# W050C.net
KiCad netlist of a schematic drawn in EAGLE
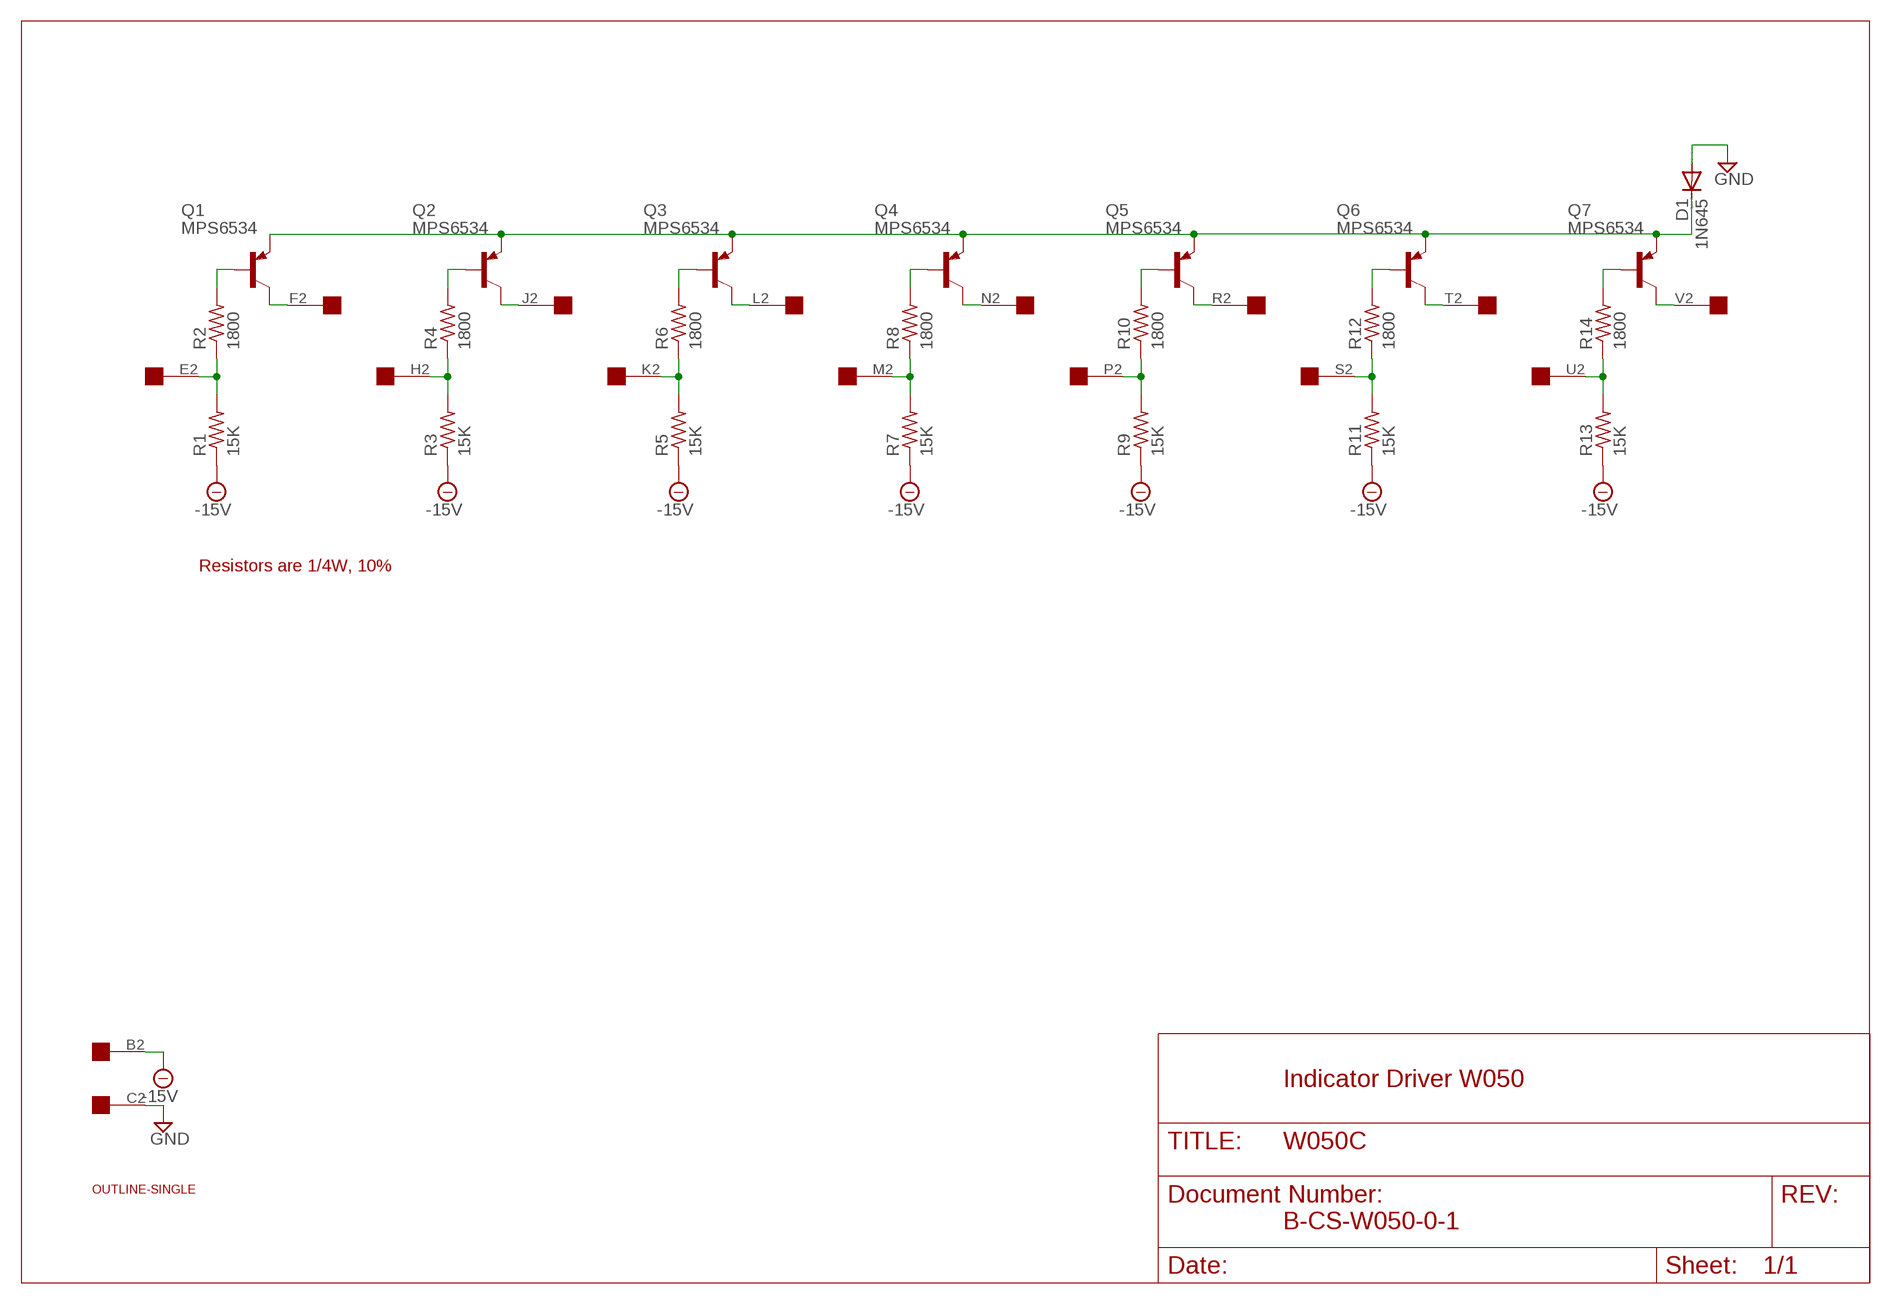
[diagram p0: schematic, sheet 1]

(export (version "E")
  (design (tool "Eeschema 10.0.6"))
  (components
    (comp (ref "D1")
      (value "1N645")
      (footprint "eagle-import:DO35-10")
      (libsource (lib "eagle-import") (part "1N4148DO35-10"))
    )
    (comp (ref "EDGE")
      (value "EDGE-1")
      (footprint "eagle-import:EDGE-CON1")
      (libsource (lib "eagle-import") (part "EDGE-1"))
    )
    (comp (ref "Q1")
      (value "MPS6534")
      (footprint "eagle-import:TO39")
      (libsource (lib "eagle-import") (part "2N2904"))
    )
    (comp (ref "Q2")
      (value "MPS6534")
      (footprint "eagle-import:TO39")
      (libsource (lib "eagle-import") (part "2N2904"))
    )
    (comp (ref "Q3")
      (value "MPS6534")
      (footprint "eagle-import:TO39")
      (libsource (lib "eagle-import") (part "2N2904"))
    )
    (comp (ref "Q4")
      (value "MPS6534")
      (footprint "eagle-import:TO39")
      (libsource (lib "eagle-import") (part "2N2904"))
    )
    (comp (ref "Q5")
      (value "MPS6534")
      (footprint "eagle-import:TO39")
      (libsource (lib "eagle-import") (part "2N2904"))
    )
    (comp (ref "Q6")
      (value "MPS6534")
      (footprint "eagle-import:TO39")
      (libsource (lib "eagle-import") (part "2N2904"))
    )
    (comp (ref "Q7")
      (value "MPS6534")
      (footprint "eagle-import:TO39")
      (libsource (lib "eagle-import") (part "2N2904"))
    )
    (comp (ref "R1")
      (value "15K")
      (footprint "eagle-import:0207_10")
      (libsource (lib "eagle-import") (part "R-US_0207/10"))
    )
    (comp (ref "R2")
      (value "1800")
      (footprint "eagle-import:0207_10")
      (libsource (lib "eagle-import") (part "R-US_0207/10"))
    )
    (comp (ref "R3")
      (value "15K")
      (footprint "eagle-import:0207_10")
      (libsource (lib "eagle-import") (part "R-US_0207/10"))
    )
    (comp (ref "R4")
      (value "1800")
      (footprint "eagle-import:0207_10")
      (libsource (lib "eagle-import") (part "R-US_0207/10"))
    )
    (comp (ref "R5")
      (value "15K")
      (footprint "eagle-import:0207_10")
      (libsource (lib "eagle-import") (part "R-US_0207/10"))
    )
    (comp (ref "R6")
      (value "1800")
      (footprint "eagle-import:0207_10")
      (libsource (lib "eagle-import") (part "R-US_0207/10"))
    )
    (comp (ref "R7")
      (value "15K")
      (footprint "eagle-import:0207_10")
      (libsource (lib "eagle-import") (part "R-US_0207/10"))
    )
    (comp (ref "R8")
      (value "1800")
      (footprint "eagle-import:0207_10")
      (libsource (lib "eagle-import") (part "R-US_0207/10"))
    )
    (comp (ref "R9")
      (value "15K")
      (footprint "eagle-import:0207_10")
      (libsource (lib "eagle-import") (part "R-US_0207/10"))
    )
    (comp (ref "R10")
      (value "1800")
      (footprint "eagle-import:0207_10")
      (libsource (lib "eagle-import") (part "R-US_0207/10"))
    )
    (comp (ref "R11")
      (value "15K")
      (footprint "eagle-import:0207_10")
      (libsource (lib "eagle-import") (part "R-US_0207/10"))
    )
    (comp (ref "R12")
      (value "1800")
      (footprint "eagle-import:0207_10")
      (libsource (lib "eagle-import") (part "R-US_0207/10"))
    )
    (comp (ref "R13")
      (value "15K")
      (footprint "eagle-import:0207_10")
      (libsource (lib "eagle-import") (part "R-US_0207/10"))
    )
    (comp (ref "R14")
      (value "1800")
      (footprint "eagle-import:0207_10")
      (libsource (lib "eagle-import") (part "R-US_0207/10"))
    )
    (comp (ref "U$1")
      (value "OUTLINE-SINGLE")
      (footprint "eagle-import:SINGLE")
      (libsource (lib "eagle-import") (part "OUTLINE-SINGLE"))
    )
  )
  (nets
    (net (code "1") (name "-15V") (class "Default")
      (node (ref "EDGE") (pin "B2") (pinfunction "1_B2") (pintype "bidirectional"))
      (node (ref "R1") (pin "1") (pinfunction "1_1") (pintype "passive"))
      (node (ref "R11") (pin "1") (pinfunction "1_1") (pintype "passive"))
      (node (ref "R13") (pin "1") (pinfunction "1_1") (pintype "passive"))
      (node (ref "R3") (pin "1") (pinfunction "1_1") (pintype "passive"))
      (node (ref "R5") (pin "1") (pinfunction "1_1") (pintype "passive"))
      (node (ref "R7") (pin "1") (pinfunction "1_1") (pintype "passive"))
      (node (ref "R9") (pin "1") (pinfunction "1_1") (pintype "passive"))
    )
    (net (code "2") (name "GND") (class "Default")
      (node (ref "D1") (pin "A") (pinfunction "A_A") (pintype "passive"))
      (node (ref "EDGE") (pin "C2") (pinfunction "1_C2") (pintype "bidirectional"))
    )
    (net (code "3") (name "Net-(EDGEE-1)") (class "Default")
      (node (ref "EDGE") (pin "E2") (pinfunction "1_E2") (pintype "bidirectional"))
      (node (ref "R1") (pin "2") (pinfunction "2_2") (pintype "passive"))
      (node (ref "R2") (pin "1") (pinfunction "1_1") (pintype "passive"))
    )
    (net (code "4") (name "Net-(EDGEF-1)") (class "Default")
      (node (ref "EDGE") (pin "F2") (pinfunction "1_F2") (pintype "bidirectional"))
      (node (ref "Q1") (pin "3") (pinfunction "C_3") (pintype "passive"))
    )
    (net (code "5") (name "Net-(EDGEG-1)") (class "Default")
      (node (ref "EDGE") (pin "H2") (pinfunction "1_H2") (pintype "bidirectional"))
      (node (ref "R3") (pin "2") (pinfunction "2_2") (pintype "passive"))
      (node (ref "R4") (pin "1") (pinfunction "1_1") (pintype "passive"))
    )
    (net (code "6") (name "Net-(EDGEH-1)") (class "Default")
      (node (ref "EDGE") (pin "J2") (pinfunction "1_J2") (pintype "bidirectional"))
      (node (ref "Q2") (pin "3") (pinfunction "C_3") (pintype "passive"))
    )
    (net (code "7") (name "Net-(EDGEI-1)") (class "Default")
      (node (ref "EDGE") (pin "K2") (pinfunction "1_K2") (pintype "bidirectional"))
      (node (ref "R5") (pin "2") (pinfunction "2_2") (pintype "passive"))
      (node (ref "R6") (pin "1") (pinfunction "1_1") (pintype "passive"))
    )
    (net (code "8") (name "Net-(EDGEJ-1)") (class "Default")
      (node (ref "EDGE") (pin "L2") (pinfunction "1_L2") (pintype "bidirectional"))
      (node (ref "Q3") (pin "3") (pinfunction "C_3") (pintype "passive"))
    )
    (net (code "9") (name "Net-(EDGEK-1)") (class "Default")
      (node (ref "EDGE") (pin "M2") (pinfunction "1_M2") (pintype "bidirectional"))
      (node (ref "R7") (pin "2") (pinfunction "2_2") (pintype "passive"))
      (node (ref "R8") (pin "1") (pinfunction "1_1") (pintype "passive"))
    )
    (net (code "10") (name "Net-(EDGEL-1)") (class "Default")
      (node (ref "EDGE") (pin "N2") (pinfunction "1_N2") (pintype "bidirectional"))
      (node (ref "Q4") (pin "3") (pinfunction "C_3") (pintype "passive"))
    )
    (net (code "11") (name "Net-(EDGEM-1)") (class "Default")
      (node (ref "EDGE") (pin "P2") (pinfunction "1_P2") (pintype "bidirectional"))
      (node (ref "R10") (pin "1") (pinfunction "1_1") (pintype "passive"))
      (node (ref "R9") (pin "2") (pinfunction "2_2") (pintype "passive"))
    )
    (net (code "12") (name "Net-(EDGEN-1)") (class "Default")
      (node (ref "EDGE") (pin "R2") (pinfunction "1_R2") (pintype "bidirectional"))
      (node (ref "Q5") (pin "3") (pinfunction "C_3") (pintype "passive"))
    )
    (net (code "13") (name "Net-(EDGEO-1)") (class "Default")
      (node (ref "EDGE") (pin "S2") (pinfunction "1_S2") (pintype "bidirectional"))
      (node (ref "R11") (pin "2") (pinfunction "2_2") (pintype "passive"))
      (node (ref "R12") (pin "1") (pinfunction "1_1") (pintype "passive"))
    )
    (net (code "14") (name "Net-(EDGEP-1)") (class "Default")
      (node (ref "EDGE") (pin "T2") (pinfunction "1_T2") (pintype "bidirectional"))
      (node (ref "Q6") (pin "3") (pinfunction "C_3") (pintype "passive"))
    )
    (net (code "15") (name "Net-(EDGEQ-1)") (class "Default")
      (node (ref "EDGE") (pin "U2") (pinfunction "1_U2") (pintype "bidirectional"))
      (node (ref "R13") (pin "2") (pinfunction "2_2") (pintype "passive"))
      (node (ref "R14") (pin "1") (pinfunction "1_1") (pintype "passive"))
    )
    (net (code "16") (name "Net-(EDGER-1)") (class "Default")
      (node (ref "EDGE") (pin "V2") (pinfunction "1_V2") (pintype "bidirectional"))
      (node (ref "Q7") (pin "3") (pinfunction "C_3") (pintype "passive"))
    )
    (net (code "17") (name "Net-(Q1-B)") (class "Default")
      (node (ref "Q1") (pin "2") (pinfunction "B_2") (pintype "passive"))
      (node (ref "R2") (pin "2") (pinfunction "2_2") (pintype "passive"))
    )
    (net (code "18") (name "Net-(Q1-E)") (class "Default")
      (node (ref "D1") (pin "C") (pinfunction "C_C") (pintype "passive"))
      (node (ref "Q1") (pin "1") (pinfunction "E_1") (pintype "passive"))
      (node (ref "Q2") (pin "1") (pinfunction "E_1") (pintype "passive"))
      (node (ref "Q3") (pin "1") (pinfunction "E_1") (pintype "passive"))
      (node (ref "Q4") (pin "1") (pinfunction "E_1") (pintype "passive"))
      (node (ref "Q5") (pin "1") (pinfunction "E_1") (pintype "passive"))
      (node (ref "Q6") (pin "1") (pinfunction "E_1") (pintype "passive"))
      (node (ref "Q7") (pin "1") (pinfunction "E_1") (pintype "passive"))
    )
    (net (code "19") (name "Net-(Q2-B)") (class "Default")
      (node (ref "Q2") (pin "2") (pinfunction "B_2") (pintype "passive"))
      (node (ref "R4") (pin "2") (pinfunction "2_2") (pintype "passive"))
    )
    (net (code "20") (name "Net-(Q3-B)") (class "Default")
      (node (ref "Q3") (pin "2") (pinfunction "B_2") (pintype "passive"))
      (node (ref "R6") (pin "2") (pinfunction "2_2") (pintype "passive"))
    )
    (net (code "21") (name "Net-(Q4-B)") (class "Default")
      (node (ref "Q4") (pin "2") (pinfunction "B_2") (pintype "passive"))
      (node (ref "R8") (pin "2") (pinfunction "2_2") (pintype "passive"))
    )
    (net (code "22") (name "Net-(Q5-B)") (class "Default")
      (node (ref "Q5") (pin "2") (pinfunction "B_2") (pintype "passive"))
      (node (ref "R10") (pin "2") (pinfunction "2_2") (pintype "passive"))
    )
    (net (code "23") (name "Net-(Q6-B)") (class "Default")
      (node (ref "Q6") (pin "2") (pinfunction "B_2") (pintype "passive"))
      (node (ref "R12") (pin "2") (pinfunction "2_2") (pintype "passive"))
    )
    (net (code "24") (name "Net-(Q7-B)") (class "Default")
      (node (ref "Q7") (pin "2") (pinfunction "B_2") (pintype "passive"))
      (node (ref "R14") (pin "2") (pinfunction "2_2") (pintype "passive"))
    )
  )
)
